# FC_RGB.net
KiCad netlist of a schematic drawn in Altium Designer
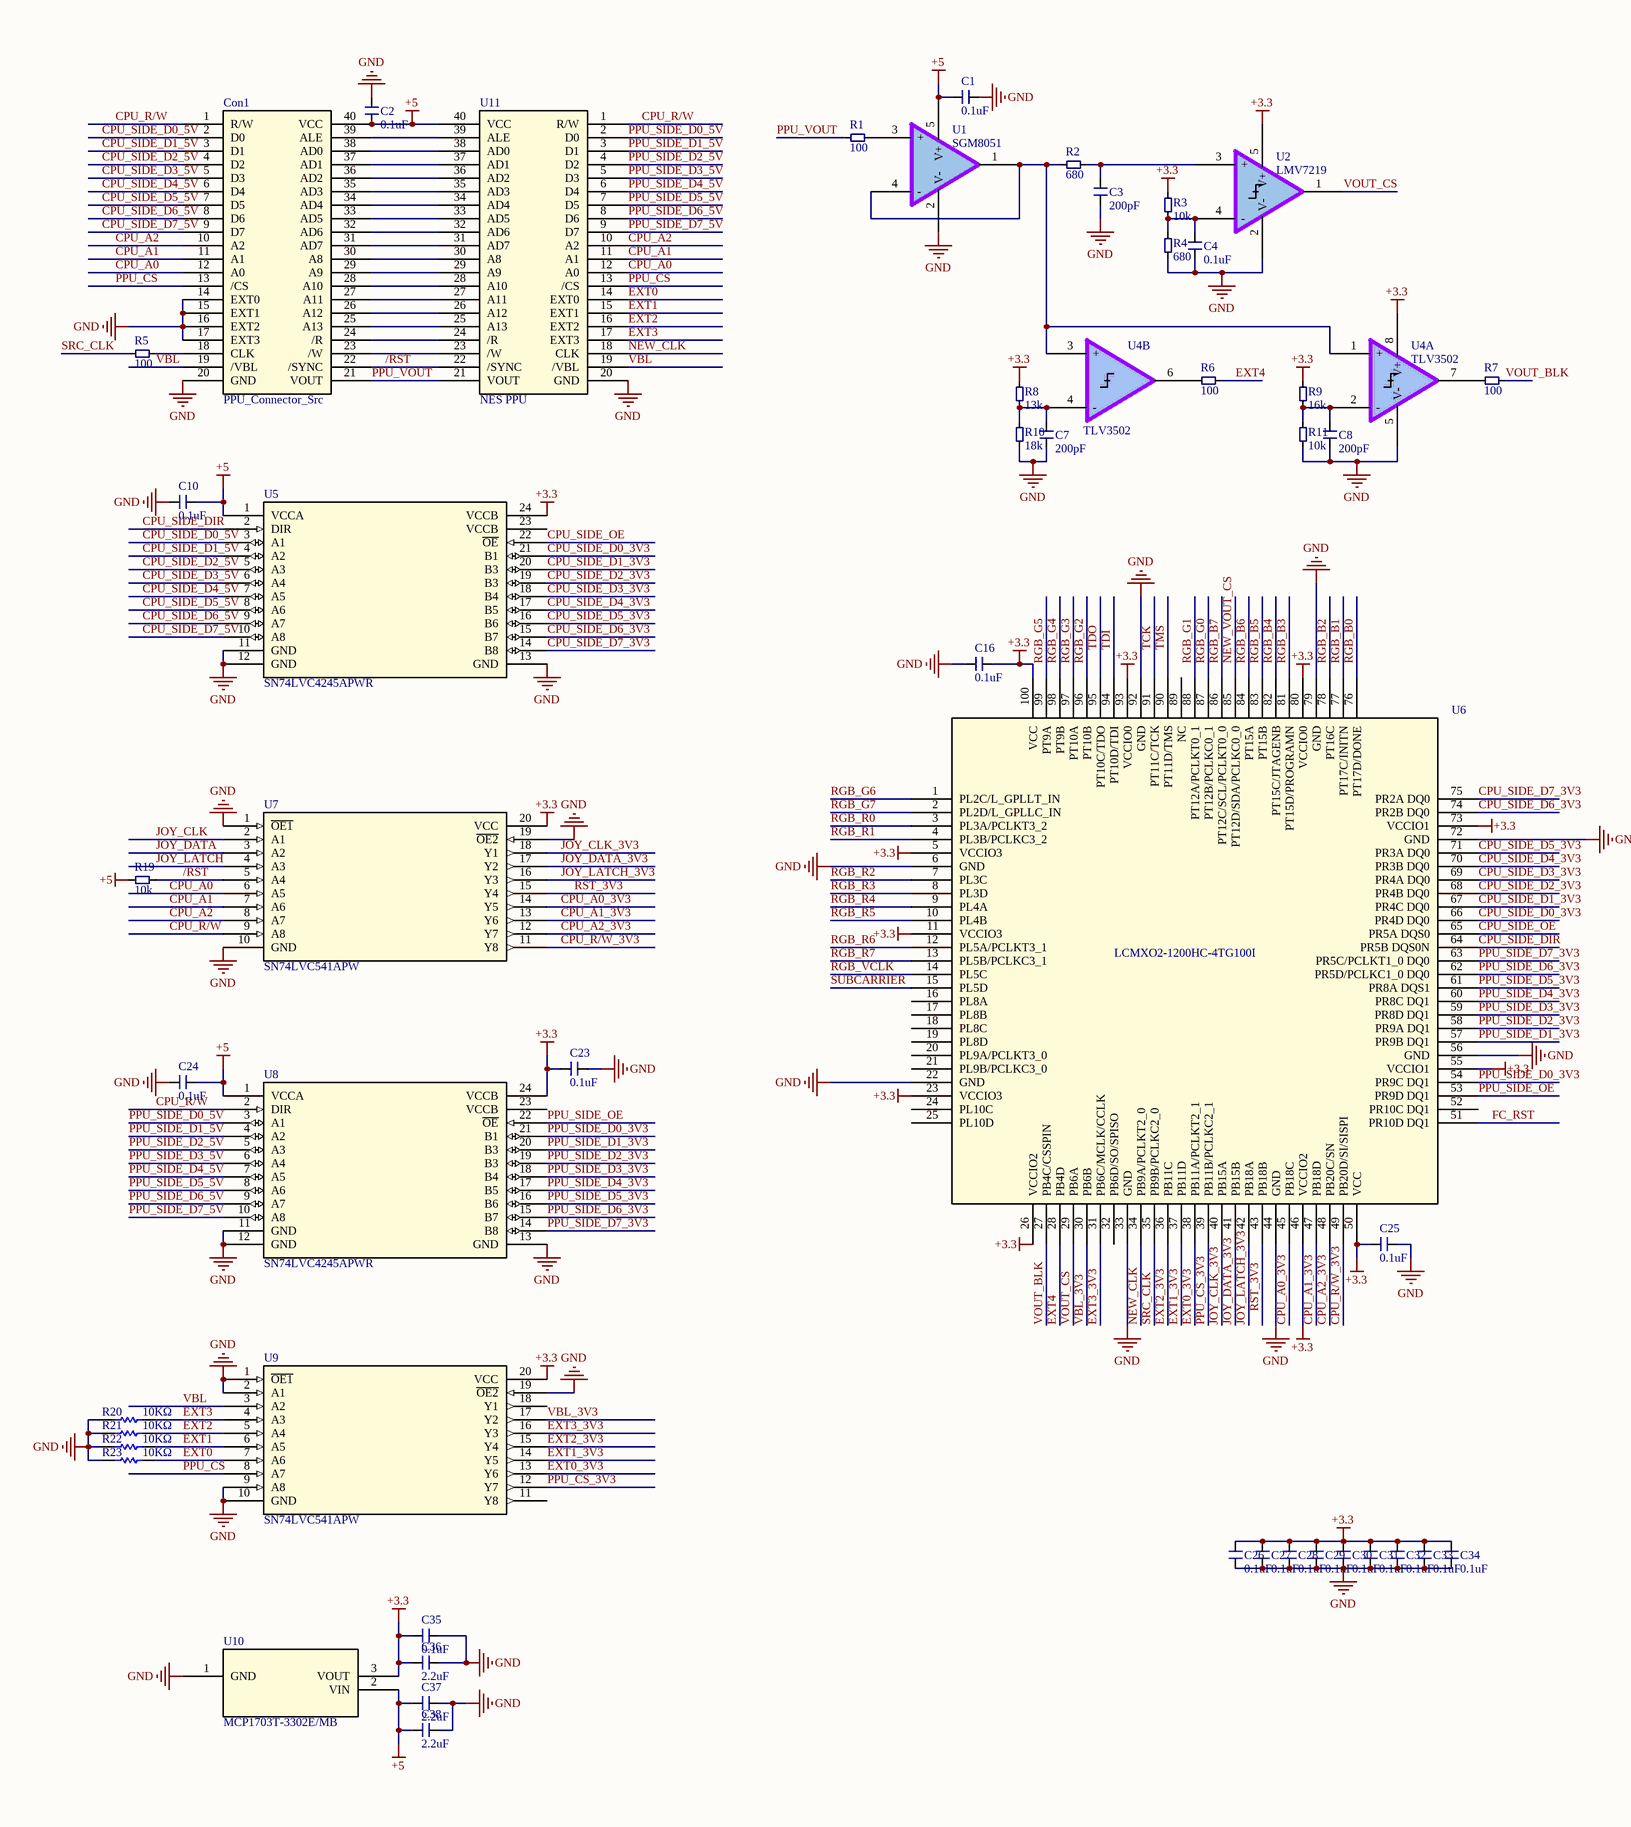
[diagram p0: FC_RGB.SchDoc, left]
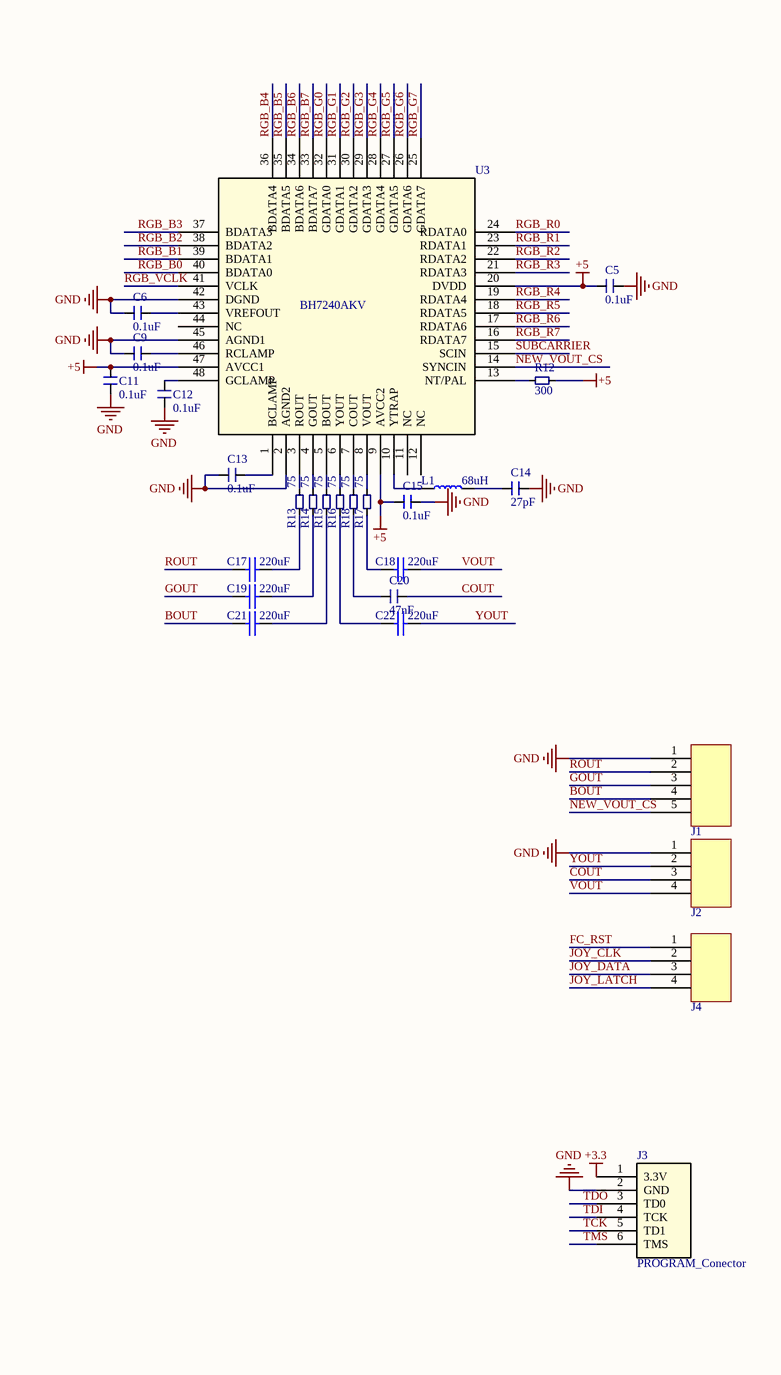
[diagram p1: FC_RGB.SchDoc, right]

(export (version "E")
  (design (tool "Eeschema 10.0.6"))
  (components
    (comp (ref "C1")
      (value "0.1uF")
      (footprint "C0402")
      (fields (field (name "Comment") "Cap"))
      (libsource (lib "Au") (part "CAP"))
    )
    (comp (ref "C2")
      (value "0.1uF")
      (footprint "C0805")
      (fields (field (name "Comment") "Cap"))
      (libsource (lib "Au") (part "CAP"))
    )
    (comp (ref "C3")
      (value "200pF")
      (footprint "C0402")
      (fields (field (name "Comment") "Cap"))
      (libsource (lib "Au") (part "CAP"))
    )
    (comp (ref "C4")
      (value "0.1uF")
      (footprint "C0402")
      (fields (field (name "Comment") "Cap"))
      (libsource (lib "Au") (part "CAP"))
    )
    (comp (ref "C5")
      (value "0.1uF")
      (footprint "C0402")
      (fields (field (name "Comment") "CAP"))
      (libsource (lib "Au") (part "CAP"))
    )
    (comp (ref "C6")
      (value "0.1uF")
      (footprint "C0402")
      (fields (field (name "Comment") "CAP"))
      (libsource (lib "Au") (part "CAP"))
    )
    (comp (ref "C7")
      (value "200pF")
      (footprint "C0402")
      (fields (field (name "Comment") "Cap"))
      (libsource (lib "Au") (part "CAP"))
    )
    (comp (ref "C8")
      (value "200pF")
      (footprint "C0402")
      (fields (field (name "Comment") "Cap"))
      (libsource (lib "Au") (part "CAP"))
    )
    (comp (ref "C9")
      (value "0.1uF")
      (footprint "C0402")
      (fields (field (name "Comment") "CAP"))
      (libsource (lib "Au") (part "CAP"))
    )
    (comp (ref "C10")
      (value "0.1uF")
      (footprint "C0402")
      (fields (field (name "Comment") "CAP"))
      (libsource (lib "Au") (part "CAP"))
    )
    (comp (ref "C11")
      (value "0.1uF")
      (footprint "C0402")
      (fields (field (name "Comment") "CAP"))
      (libsource (lib "Au") (part "CAP"))
    )
    (comp (ref "C12")
      (value "0.1uF")
      (footprint "C0402")
      (fields (field (name "Comment") "CAP"))
      (libsource (lib "Au") (part "CAP"))
    )
    (comp (ref "C13")
      (value "0.1uF")
      (footprint "C0402")
      (fields (field (name "Comment") "CAP"))
      (libsource (lib "Au") (part "CAP"))
    )
    (comp (ref "C14")
      (value "27pF")
      (footprint "C0402")
      (fields (field (name "Comment") "CAP"))
      (libsource (lib "Au") (part "CAP"))
    )
    (comp (ref "C15")
      (value "0.1uF")
      (footprint "C0402")
      (fields (field (name "Comment") "CAP"))
      (libsource (lib "Au") (part "CAP"))
    )
    (comp (ref "C16")
      (value "0.1uF")
      (footprint "C0402")
      (fields (field (name "Comment") "Cap"))
      (libsource (lib "Au") (part "CAP"))
    )
    (comp (ref "C17")
      (value "220uF")
      (footprint "C 1206_L")
      (description "No Description Available")
      (fields
        (field (name "MANUFACTURER_PART_NUMBER") "C0603X394K4RACAUTO")
        (field (name "COPYRIGHT") "Copyright (C) 2022 Ultra Librarian. All rights reserved.")
      )
      (libsource (lib "FC_Extends") (part "C1206"))
    )
    (comp (ref "C18")
      (value "220uF")
      (footprint "C 1206_L")
      (description "No Description Available")
      (fields
        (field (name "MANUFACTURER_PART_NUMBER") "C0603X394K4RACAUTO")
        (field (name "COPYRIGHT") "Copyright (C) 2022 Ultra Librarian. All rights reserved.")
      )
      (libsource (lib "FC_Extends") (part "C1206"))
    )
    (comp (ref "C19")
      (value "220uF")
      (footprint "C 1206_L")
      (description "No Description Available")
      (fields
        (field (name "MANUFACTURER_PART_NUMBER") "C0603X394K4RACAUTO")
        (field (name "COPYRIGHT") "Copyright (C) 2022 Ultra Librarian. All rights reserved.")
      )
      (libsource (lib "FC_Extends") (part "C1206"))
    )
    (comp (ref "C20")
      (value "47nF")
      (footprint "C0402")
      (fields (field (name "Comment") "CAP"))
      (libsource (lib "Au") (part "CAP"))
    )
    (comp (ref "C21")
      (value "220uF")
      (footprint "C 1206_L")
      (description "No Description Available")
      (fields
        (field (name "MANUFACTURER_PART_NUMBER") "C0603X394K4RACAUTO")
        (field (name "COPYRIGHT") "Copyright (C) 2022 Ultra Librarian. All rights reserved.")
      )
      (libsource (lib "FC_Extends") (part "C1206"))
    )
    (comp (ref "C22")
      (value "220uF")
      (footprint "C 1206_L")
      (description "No Description Available")
      (fields
        (field (name "MANUFACTURER_PART_NUMBER") "C0603X394K4RACAUTO")
        (field (name "COPYRIGHT") "Copyright (C) 2022 Ultra Librarian. All rights reserved.")
      )
      (libsource (lib "FC_Extends") (part "C1206"))
    )
    (comp (ref "C23")
      (value "0.1uF")
      (footprint "C0402")
      (fields (field (name "Comment") "CAP"))
      (libsource (lib "Au") (part "CAP"))
    )
    (comp (ref "C24")
      (value "0.1uF")
      (footprint "C0402")
      (fields (field (name "Comment") "CAP"))
      (libsource (lib "Au") (part "CAP"))
    )
    (comp (ref "C25")
      (value "0.1uF")
      (footprint "C0402")
      (fields (field (name "Comment") "Cap"))
      (libsource (lib "Au") (part "CAP"))
    )
    (comp (ref "C26")
      (value "0.1uF")
      (footprint "C0402")
      (fields (field (name "Comment") "CAP"))
      (libsource (lib "Au") (part "CAP"))
    )
    (comp (ref "C27")
      (value "0.1uF")
      (footprint "C0402")
      (fields (field (name "Comment") "CAP"))
      (libsource (lib "Au") (part "CAP"))
    )
    (comp (ref "C28")
      (value "0.1uF")
      (footprint "C0402")
      (fields (field (name "Comment") "CAP"))
      (libsource (lib "Au") (part "CAP"))
    )
    (comp (ref "C29")
      (value "0.1uF")
      (footprint "C0402")
      (fields (field (name "Comment") "CAP"))
      (libsource (lib "Au") (part "CAP"))
    )
    (comp (ref "C30")
      (value "0.1uF")
      (footprint "C0402")
      (fields (field (name "Comment") "CAP"))
      (libsource (lib "Au") (part "CAP"))
    )
    (comp (ref "C31")
      (value "0.1uF")
      (footprint "C0402")
      (fields (field (name "Comment") "CAP"))
      (libsource (lib "Au") (part "CAP"))
    )
    (comp (ref "C32")
      (value "0.1uF")
      (footprint "C0402")
      (fields (field (name "Comment") "CAP"))
      (libsource (lib "Au") (part "CAP"))
    )
    (comp (ref "C33")
      (value "0.1uF")
      (footprint "C0402")
      (fields (field (name "Comment") "CAP"))
      (libsource (lib "Au") (part "CAP"))
    )
    (comp (ref "C34")
      (value "0.1uF")
      (footprint "C0402")
      (fields (field (name "Comment") "CAP"))
      (libsource (lib "Au") (part "CAP"))
    )
    (comp (ref "C35")
      (value "0.1uF")
      (footprint "C0603")
      (fields (field (name "Comment") "Cap"))
      (libsource (lib "Au") (part "CAP"))
    )
    (comp (ref "C36")
      (value "2.2uF")
      (footprint "C0603")
      (fields (field (name "Comment") "Cap"))
      (libsource (lib "Au") (part "CAP"))
    )
    (comp (ref "C37")
      (value "2.2uF")
      (footprint "C0805")
      (fields (field (name "Comment") "Cap"))
      (libsource (lib "Au") (part "CAP"))
    )
    (comp (ref "C38")
      (value "2.2uF")
      (footprint "C0805")
      (fields (field (name "Comment") "Cap"))
      (libsource (lib "Au") (part "CAP"))
    )
    (comp (ref "Con1")
      (value "PPU_Connector_Src")
      (footprint "DIP40_SRC")
      (libsource (lib "FC_Extends") (part "PPU_Connector_Src"))
    )
    (comp (ref "J1") (value "CN") (footprint "CN5_1.25_90") (libsource (lib "Au") (part "CN5")))
    (comp (ref "J2") (value "CN") (footprint "CN4_1.25_90") (libsource (lib "Au") (part "CN4")))
    (comp (ref "J3")
      (value "PROGRAM_Conector")
      (footprint "CON_PROGRAM")
      (libsource (lib "FC_Extends") (part "PROGRAM_Conector"))
    )
    (comp (ref "J4") (value "CN") (footprint "CN4_1.25_90") (libsource (lib "Au") (part "CN4")))
    (comp (ref "L1") (value "68uH") (footprint "L 0805") (libsource (lib "FC_Extends") (part "L0805")))
    (comp (ref "R1")
      (value "100")
      (footprint "R-0402")
      (fields (field (name "Comment") "RES_SMD"))
      (libsource (lib "Au") (part "RES_SMD"))
    )
    (comp (ref "R2")
      (value "680")
      (footprint "R-0402")
      (fields (field (name "Comment") "RES_SMD"))
      (libsource (lib "Au") (part "RES_SMD"))
    )
    (comp (ref "R3")
      (value "10k")
      (footprint "R-0402")
      (fields (field (name "Comment") "RES_SMD"))
      (libsource (lib "Au") (part "RES_SMD"))
    )
    (comp (ref "R4")
      (value "680")
      (footprint "R-0402")
      (fields (field (name "Comment") "RES_SMD"))
      (libsource (lib "Au") (part "RES_SMD"))
    )
    (comp (ref "R5")
      (value "100")
      (footprint "R-0402")
      (fields (field (name "Comment") "RES_SMD"))
      (libsource (lib "Au") (part "RES_SMD"))
    )
    (comp (ref "R6")
      (value "100")
      (footprint "R-0402")
      (fields (field (name "Comment") "RES_SMD"))
      (libsource (lib "Au") (part "RES_SMD"))
    )
    (comp (ref "R7")
      (value "100")
      (footprint "R-0402")
      (fields (field (name "Comment") "RES_SMD"))
      (libsource (lib "Au") (part "RES_SMD"))
    )
    (comp (ref "R8")
      (value "13k")
      (footprint "R-0402")
      (fields (field (name "Comment") "RES_SMD"))
      (libsource (lib "Au") (part "RES_SMD"))
    )
    (comp (ref "R9")
      (value "16k")
      (footprint "R-0402")
      (fields (field (name "Comment") "RES_SMD"))
      (libsource (lib "Au") (part "RES_SMD"))
    )
    (comp (ref "R10")
      (value "18k")
      (footprint "R-0402")
      (fields (field (name "Comment") "RES_SMD"))
      (libsource (lib "Au") (part "RES_SMD"))
    )
    (comp (ref "R11")
      (value "10k")
      (footprint "R-0402")
      (fields (field (name "Comment") "RES_SMD"))
      (libsource (lib "Au") (part "RES_SMD"))
    )
    (comp (ref "R12")
      (value "300")
      (footprint "R-0402")
      (fields (field (name "Comment") "RES_SMD"))
      (libsource (lib "Au") (part "RES_SMD"))
    )
    (comp (ref "R13")
      (value "75")
      (footprint "R-0402")
      (fields (field (name "Comment") "RES_SMD"))
      (libsource (lib "Au") (part "RES_SMD"))
    )
    (comp (ref "R14")
      (value "75")
      (footprint "R-0402")
      (fields (field (name "Comment") "RES_SMD"))
      (libsource (lib "Au") (part "RES_SMD"))
    )
    (comp (ref "R15")
      (value "75")
      (footprint "R-0402")
      (fields (field (name "Comment") "RES_SMD"))
      (libsource (lib "Au") (part "RES_SMD"))
    )
    (comp (ref "R16")
      (value "75")
      (footprint "R-0402")
      (fields (field (name "Comment") "RES_SMD"))
      (libsource (lib "Au") (part "RES_SMD"))
    )
    (comp (ref "R17")
      (value "75")
      (footprint "R-0402")
      (fields (field (name "Comment") "RES_SMD"))
      (libsource (lib "Au") (part "RES_SMD"))
    )
    (comp (ref "R18")
      (value "75")
      (footprint "R-0402")
      (fields (field (name "Comment") "RES_SMD"))
      (libsource (lib "Au") (part "RES_SMD"))
    )
    (comp (ref "R19")
      (value "10k")
      (footprint "R-0402")
      (fields (field (name "Comment") "RES_SMD"))
      (libsource (lib "Au") (part "RES_SMD"))
    )
    (comp (ref "R20")
      (value "10KΩ")
      (footprint "0603_R")
      (description "No Description Available")
      (fields
        (field (name "MANUFACTURER_PART_NUMBER") "RC0603FR-07200RL")
        (field (name "COPYRIGHT") "Copyright (C) 2022 Ultra Librarian. All rights reserved.")
      )
      (libsource (lib "FC_Extends") (part "R0603"))
    )
    (comp (ref "R21")
      (value "10KΩ")
      (footprint "0603_R")
      (description "No Description Available")
      (fields
        (field (name "MANUFACTURER_PART_NUMBER") "RC0603FR-07200RL")
        (field (name "COPYRIGHT") "Copyright (C) 2022 Ultra Librarian. All rights reserved.")
      )
      (libsource (lib "FC_Extends") (part "R0603"))
    )
    (comp (ref "R22")
      (value "10KΩ")
      (footprint "0603_R")
      (description "No Description Available")
      (fields
        (field (name "MANUFACTURER_PART_NUMBER") "RC0603FR-07200RL")
        (field (name "COPYRIGHT") "Copyright (C) 2022 Ultra Librarian. All rights reserved.")
      )
      (libsource (lib "FC_Extends") (part "R0603"))
    )
    (comp (ref "R23")
      (value "10KΩ")
      (footprint "0603_R")
      (description "No Description Available")
      (fields
        (field (name "MANUFACTURER_PART_NUMBER") "RC0603FR-07200RL")
        (field (name "COPYRIGHT") "Copyright (C) 2022 Ultra Librarian. All rights reserved.")
      )
      (libsource (lib "FC_Extends") (part "R0603"))
    )
    (comp (ref "U1")
      (value "SGM8051")
      (footprint "SOT-23-5")
      (description "High Speed OpAmp")
      (libsource (lib "Au") (part "SGM8051"))
    )
    (comp (ref "U2")
      (value "LMV7219")
      (footprint "SOT-23-5")
      (description "High Speed Comparator")
      (libsource (lib "Au") (part "LMV7219"))
    )
    (comp (ref "U3")
      (value "BH7240AKV")
      (footprint "LQFP48-7*7")
      (description "No Description Available")
      (fields
        (field (name "MANUFACTURER_PART_NUMBER") "ADV7123JSTZ330")
        (field (name "COPYRIGHT") "Copyright (C) 2022 Ultra Librarian. All rights reserved.")
      )
      (libsource (lib "FC_Extends") (part "BH7240AKV"))
    )
    (comp (ref "U4")
      (value "TLV3502")
      (footprint "SOP-8-SMALL")
      (description "4.5ns Dual High-Speed Comparator")
      (libsource (lib "Au") (part "TLV3502"))
    )
    (comp (ref "U5")
      (value "SN74LVC4245APWR")
      (footprint "TSSOP24")
      (description "LJ245A")
      (fields (field (name "COPYRIGHT") "Copyright (C) 2022 Ultra Librarian. All rights reserved."))
      (libsource (lib "Au") (part "74LVC4245"))
    )
    (comp (ref "U6")
      (value "LCMXO2-1200HC-4TG100I")
      (footprint "TQFP100_LAT")
      (description "No Description Available")
      (fields (field (name "COPYRIGHT") "Copyright (C) 2023 Ultra Librarian. All rights reserved."))
      (libsource (lib "FC_Extends") (part "LCMXO2-1200HC"))
    )
    (comp (ref "U7")
      (value "SN74LVC541APW")
      (footprint "TSSOP20")
      (description "LC541A")
      (fields (field (name "COPYRIGHT") "Copyright (C) 2022 Ultra Librarian. All rights reserved."))
      (libsource (lib "Au") (part "74LVC541"))
    )
    (comp (ref "U8")
      (value "SN74LVC4245APWR")
      (footprint "TSSOP24")
      (description "LJ245A")
      (fields (field (name "COPYRIGHT") "Copyright (C) 2022 Ultra Librarian. All rights reserved."))
      (libsource (lib "Au") (part "74LVC4245"))
    )
    (comp (ref "U9")
      (value "SN74LVC541APW")
      (footprint "TSSOP20")
      (description "LC541A")
      (fields (field (name "COPYRIGHT") "Copyright (C) 2022 Ultra Librarian. All rights reserved."))
      (libsource (lib "Au") (part "74LVC541"))
    )
    (comp (ref "U10")
      (value "MCP1703T-3302E/MB")
      (footprint "SOT-89_3MC_MCH")
      (description "No Description Available")
      (fields (field (name "COPYRIGHT") "Copyright (C) 2022 Ultra Librarian. All rights reserved."))
      (libsource (lib "FC_Extends") (part "MCP1703T-3302E/MB"))
    )
    (comp (ref "U11")
      (value "NES PPU")
      (footprint "PDIP-40-BP")
      (description "NES PPU RP2C02")
      (libsource (lib "Au") (part "RP2C02"))
    )
  )
  (nets
    (net (code "1") (name "+3.3") (class "Default")
      (node (ref "C16") (pin "2") (pintype "power_in"))
      (node (ref "C23") (pin "2") (pintype "power_in"))
      (node (ref "C25") (pin "1") (pintype "power_in"))
      (node (ref "C26") (pin "1") (pintype "power_in"))
      (node (ref "C27") (pin "1") (pintype "power_in"))
      (node (ref "C28") (pin "1") (pintype "power_in"))
      (node (ref "C29") (pin "1") (pintype "power_in"))
      (node (ref "C30") (pin "1") (pintype "power_in"))
      (node (ref "C31") (pin "1") (pintype "power_in"))
      (node (ref "C32") (pin "1") (pintype "power_in"))
      (node (ref "C33") (pin "1") (pintype "power_in"))
      (node (ref "C34") (pin "1") (pintype "power_in"))
      (node (ref "C35") (pin "1") (pintype "power_in"))
      (node (ref "C36") (pin "1") (pintype "power_in"))
      (node (ref "J3") (pin "1") (pinfunction "3.3V_1") (pintype "passive"))
      (node (ref "R3") (pin "2") (pintype "passive"))
      (node (ref "R8") (pin "2") (pintype "passive"))
      (node (ref "R9") (pin "2") (pintype "passive"))
      (node (ref "U10") (pin "3") (pinfunction "VOUT_3") (pintype "passive"))
      (node (ref "U2") (pin "5") (pinfunction "V+_5") (pintype "passive"))
      (node (ref "U4") (pin "8") (pinfunction "V+_8") (pintype "passive"))
      (node (ref "U5") (pin "24") (pinfunction "VCCB_24") (pintype "power_in"))
      (node (ref "U6") (pin "100") (pinfunction "VCC_100") (pintype "power_in"))
      (node (ref "U6") (pin "11") (pinfunction "VCCIO3_11") (pintype "power_in"))
      (node (ref "U6") (pin "23") (pinfunction "VCCIO3_23") (pintype "power_in"))
      (node (ref "U6") (pin "26") (pinfunction "VCCIO2_26") (pintype "power_in"))
      (node (ref "U6") (pin "46") (pinfunction "VCCIO2_46") (pintype "power_in"))
      (node (ref "U6") (pin "5") (pinfunction "VCCIO3_5") (pintype "power_in"))
      (node (ref "U6") (pin "50") (pinfunction "VCC_50") (pintype "power_in"))
      (node (ref "U6") (pin "55") (pinfunction "VCCIO1_55") (pintype "power_in"))
      (node (ref "U6") (pin "73") (pinfunction "VCCIO1_73") (pintype "power_in"))
      (node (ref "U6") (pin "80") (pinfunction "VCCIO0_80") (pintype "power_in"))
      (node (ref "U6") (pin "93") (pinfunction "VCCIO0_93") (pintype "power_in"))
      (node (ref "U7") (pin "20") (pinfunction "VCC_20") (pintype "power_in"))
      (node (ref "U8") (pin "24") (pinfunction "VCCB_24") (pintype "power_in"))
      (node (ref "U9") (pin "20") (pinfunction "VCC_20") (pintype "power_in"))
    )
    (net (code "2") (name "+5") (class "Default")
      (node (ref "C1") (pin "1") (pintype "power_in"))
      (node (ref "C10") (pin "1") (pintype "power_in"))
      (node (ref "C11") (pin "2") (pintype "power_in"))
      (node (ref "C15") (pin "2") (pintype "power_in"))
      (node (ref "C2") (pin "1") (pintype "power_in"))
      (node (ref "C24") (pin "1") (pintype "power_in"))
      (node (ref "C37") (pin "1") (pintype "power_in"))
      (node (ref "C38") (pin "1") (pintype "power_in"))
      (node (ref "C5") (pin "2") (pintype "power_in"))
      (node (ref "Con1") (pin "40") (pinfunction "VCC_40") (pintype "passive"))
      (node (ref "R12") (pin "1") (pintype "passive"))
      (node (ref "R19") (pin "2") (pintype "passive"))
      (node (ref "U1") (pin "5") (pinfunction "V+_5") (pintype "passive"))
      (node (ref "U10") (pin "2") (pinfunction "VIN_2") (pintype "passive"))
      (node (ref "U11") (pin "40") (pinfunction "VCC_40") (pintype "passive"))
      (node (ref "U3") (pin "20") (pinfunction "DVDD_20") (pintype "passive"))
      (node (ref "U3") (pin "47") (pinfunction "AVCC1_47") (pintype "passive"))
      (node (ref "U3") (pin "9") (pinfunction "AVCC2_9") (pintype "passive"))
      (node (ref "U5") (pin "1") (pinfunction "VCCA_1") (pintype "power_in"))
      (node (ref "U8") (pin "1") (pinfunction "VCCA_1") (pintype "power_in"))
    )
    (net (code "3") (name "/BOUT") (class "Default")
      (node (ref "C21") (pin "2") (pinfunction "2_2") (pintype "passive"))
      (node (ref "J1") (pin "4") (pintype "passive"))
    )
    (net (code "4") (name "/COUT") (class "Default")
      (node (ref "C20") (pin "1") (pintype "power_in"))
      (node (ref "J2") (pin "3") (pintype "passive"))
    )
    (net (code "5") (name "/CPU_A0") (class "Default")
      (node (ref "Con1") (pin "12") (pinfunction "A0_12") (pintype "passive"))
      (node (ref "U11") (pin "12") (pinfunction "A0_12") (pintype "passive"))
      (node (ref "U7") (pin "6") (pinfunction "A5_6") (pintype "input"))
    )
    (net (code "6") (name "/CPU_A0_3V3") (class "Default")
      (node (ref "U6") (pin "45") (pinfunction "PB18C_45") (pintype "passive"))
      (node (ref "U7") (pin "14") (pinfunction "Y5_14") (pintype "output"))
    )
    (net (code "7") (name "/CPU_A1") (class "Default")
      (node (ref "Con1") (pin "11") (pinfunction "A1_11") (pintype "passive"))
      (node (ref "U11") (pin "11") (pinfunction "A1_11") (pintype "passive"))
      (node (ref "U7") (pin "7") (pinfunction "A6_7") (pintype "input"))
    )
    (net (code "8") (name "/CPU_A1_3V3") (class "Default")
      (node (ref "U6") (pin "47") (pinfunction "PB18D_47") (pintype "passive"))
      (node (ref "U7") (pin "13") (pinfunction "Y6_13") (pintype "output"))
    )
    (net (code "9") (name "/CPU_A2") (class "Default")
      (node (ref "Con1") (pin "10") (pinfunction "A2_10") (pintype "passive"))
      (node (ref "U11") (pin "10") (pinfunction "A2_10") (pintype "passive"))
      (node (ref "U7") (pin "8") (pinfunction "A7_8") (pintype "input"))
    )
    (net (code "10") (name "/CPU_A2_3V3") (class "Default")
      (node (ref "U6") (pin "48") (pinfunction "PB20C/SN_48") (pintype "passive"))
      (node (ref "U7") (pin "12") (pinfunction "Y7_12") (pintype "output"))
    )
    (net (code "11") (name "/CPU_R{slash}W") (class "Default")
      (node (ref "Con1") (pin "1") (pinfunction "R/W_1") (pintype "passive"))
      (node (ref "U11") (pin "1") (pinfunction "R/W_1") (pintype "passive"))
      (node (ref "U7") (pin "9") (pinfunction "A8_9") (pintype "input"))
      (node (ref "U8") (pin "2") (pinfunction "DIR_2") (pintype "input"))
    )
    (net (code "12") (name "/CPU_R{slash}W_3V3") (class "Default")
      (node (ref "U6") (pin "49") (pinfunction "PB20D/SI/SISPI_49") (pintype "passive"))
      (node (ref "U7") (pin "11") (pinfunction "Y8_11") (pintype "output"))
    )
    (net (code "13") (name "/CPU_SIDE_D0_3V3") (class "Default")
      (node (ref "U5") (pin "21") (pinfunction "B1_21") (pintype "bidirectional"))
      (node (ref "U6") (pin "66") (pinfunction "PR4D_DQ0_66") (pintype "passive"))
    )
    (net (code "14") (name "/CPU_SIDE_D0_5V") (class "Default")
      (node (ref "Con1") (pin "2") (pinfunction "D0_2") (pintype "passive"))
      (node (ref "U5") (pin "3") (pinfunction "A1_3") (pintype "bidirectional"))
    )
    (net (code "15") (name "/CPU_SIDE_D1_3V3") (class "Default")
      (node (ref "U5") (pin "20") (pinfunction "B3_20") (pintype "bidirectional"))
      (node (ref "U6") (pin "67") (pinfunction "PR4C_DQ0_67") (pintype "passive"))
    )
    (net (code "16") (name "/CPU_SIDE_D1_5V") (class "Default")
      (node (ref "Con1") (pin "3") (pinfunction "D1_3") (pintype "passive"))
      (node (ref "U5") (pin "4") (pinfunction "A2_4") (pintype "bidirectional"))
    )
    (net (code "17") (name "/CPU_SIDE_D2_3V3") (class "Default")
      (node (ref "U5") (pin "19") (pinfunction "B3_19") (pintype "bidirectional"))
      (node (ref "U6") (pin "68") (pinfunction "PR4B_DQ0_68") (pintype "passive"))
    )
    (net (code "18") (name "/CPU_SIDE_D2_5V") (class "Default")
      (node (ref "Con1") (pin "4") (pinfunction "D2_4") (pintype "passive"))
      (node (ref "U5") (pin "5") (pinfunction "A3_5") (pintype "bidirectional"))
    )
    (net (code "19") (name "/CPU_SIDE_D3_3V3") (class "Default")
      (node (ref "U5") (pin "18") (pinfunction "B4_18") (pintype "bidirectional"))
      (node (ref "U6") (pin "69") (pinfunction "PR4A_DQ0_69") (pintype "passive"))
    )
    (net (code "20") (name "/CPU_SIDE_D3_5V") (class "Default")
      (node (ref "Con1") (pin "5") (pinfunction "D3_5") (pintype "passive"))
      (node (ref "U5") (pin "6") (pinfunction "A4_6") (pintype "bidirectional"))
    )
    (net (code "21") (name "/CPU_SIDE_D4_3V3") (class "Default")
      (node (ref "U5") (pin "17") (pinfunction "B5_17") (pintype "bidirectional"))
      (node (ref "U6") (pin "70") (pinfunction "PR3B_DQ0_70") (pintype "passive"))
    )
    (net (code "22") (name "/CPU_SIDE_D4_5V") (class "Default")
      (node (ref "Con1") (pin "6") (pinfunction "D4_6") (pintype "passive"))
      (node (ref "U5") (pin "7") (pinfunction "A5_7") (pintype "bidirectional"))
    )
    (net (code "23") (name "/CPU_SIDE_D5_3V3") (class "Default")
      (node (ref "U5") (pin "16") (pinfunction "B6_16") (pintype "bidirectional"))
      (node (ref "U6") (pin "71") (pinfunction "PR3A_DQ0_71") (pintype "passive"))
    )
    (net (code "24") (name "/CPU_SIDE_D5_5V") (class "Default")
      (node (ref "Con1") (pin "7") (pinfunction "D5_7") (pintype "passive"))
      (node (ref "U5") (pin "8") (pinfunction "A6_8") (pintype "bidirectional"))
    )
    (net (code "25") (name "/CPU_SIDE_D6_3V3") (class "Default")
      (node (ref "U5") (pin "15") (pinfunction "B7_15") (pintype "bidirectional"))
      (node (ref "U6") (pin "74") (pinfunction "PR2B_DQ0_74") (pintype "passive"))
    )
    (net (code "26") (name "/CPU_SIDE_D6_5V") (class "Default")
      (node (ref "Con1") (pin "8") (pinfunction "D6_8") (pintype "passive"))
      (node (ref "U5") (pin "9") (pinfunction "A7_9") (pintype "bidirectional"))
    )
    (net (code "27") (name "/CPU_SIDE_D7_3V3") (class "Default")
      (node (ref "U5") (pin "14") (pinfunction "B8_14") (pintype "bidirectional"))
      (node (ref "U6") (pin "75") (pinfunction "PR2A_DQ0_75") (pintype "passive"))
    )
    (net (code "28") (name "/CPU_SIDE_D7_5V") (class "Default")
      (node (ref "Con1") (pin "9") (pinfunction "D7_9") (pintype "passive"))
      (node (ref "U5") (pin "10") (pinfunction "A8_10") (pintype "bidirectional"))
    )
    (net (code "29") (name "/CPU_SIDE_DIR") (class "Default")
      (node (ref "U5") (pin "2") (pinfunction "DIR_2") (pintype "input"))
      (node (ref "U6") (pin "64") (pinfunction "PR5B_DQS0N_64") (pintype "passive"))
    )
    (net (code "30") (name "/CPU_SIDE_OE") (class "Default")
      (node (ref "U5") (pin "22") (pinfunction "~{OE}_22") (pintype "input"))
      (node (ref "U6") (pin "65") (pinfunction "PR5A_DQS0_65") (pintype "passive"))
    )
    (net (code "31") (name "/EXT0") (class "Default")
      (node (ref "R23") (pin "2") (pinfunction "2_2") (pintype "passive"))
      (node (ref "U11") (pin "14") (pinfunction "EXT0_14") (pintype "passive"))
      (node (ref "U9") (pin "7") (pinfunction "A6_7") (pintype "input"))
    )
    (net (code "32") (name "/EXT0_3V3") (class "Default")
      (node (ref "U6") (pin "38") (pinfunction "PB11A/PCLKT2_1_38") (pintype "passive"))
      (node (ref "U9") (pin "13") (pinfunction "Y6_13") (pintype "output"))
    )
    (net (code "33") (name "/EXT1") (class "Default")
      (node (ref "R22") (pin "2") (pinfunction "2_2") (pintype "passive"))
      (node (ref "U11") (pin "15") (pinfunction "EXT1_15") (pintype "passive"))
      (node (ref "U9") (pin "6") (pinfunction "A5_6") (pintype "input"))
    )
    (net (code "34") (name "/EXT1_3V3") (class "Default")
      (node (ref "U6") (pin "37") (pinfunction "PB11D_37") (pintype "passive"))
      (node (ref "U9") (pin "14") (pinfunction "Y5_14") (pintype "output"))
    )
    (net (code "35") (name "/EXT2") (class "Default")
      (node (ref "R21") (pin "2") (pinfunction "2_2") (pintype "passive"))
      (node (ref "U11") (pin "16") (pinfunction "EXT2_16") (pintype "passive"))
      (node (ref "U9") (pin "5") (pinfunction "A4_5") (pintype "input"))
    )
    (net (code "36") (name "/EXT2_3V3") (class "Default")
      (node (ref "U6") (pin "36") (pinfunction "PB11C_36") (pintype "passive"))
      (node (ref "U9") (pin "15") (pinfunction "Y4_15") (pintype "output"))
    )
    (net (code "37") (name "/EXT3") (class "Default")
      (node (ref "R20") (pin "2") (pinfunction "2_2") (pintype "passive"))
      (node (ref "U11") (pin "17") (pinfunction "EXT3_17") (pintype "passive"))
      (node (ref "U9") (pin "4") (pinfunction "A3_4") (pintype "input"))
    )
    (net (code "38") (name "/EXT3_3V3") (class "Default")
      (node (ref "U6") (pin "31") (pinfunction "PB6C/MCLK/CCLK_31") (pintype "passive"))
      (node (ref "U9") (pin "16") (pinfunction "Y3_16") (pintype "output"))
    )
    (net (code "39") (name "/EXT4") (class "Default")
      (node (ref "R6") (pin "1") (pintype "passive"))
      (node (ref "U6") (pin "28") (pinfunction "PB4D_28") (pintype "passive"))
    )
    (net (code "40") (name "/FC_RST") (class "Default")
      (node (ref "J4") (pin "1") (pintype "passive"))
      (node (ref "U6") (pin "51") (pinfunction "PR10D_DQ1_51") (pintype "passive"))
    )
    (net (code "41") (name "/GOUT") (class "Default")
      (node (ref "C19") (pin "2") (pinfunction "2_2") (pintype "passive"))
      (node (ref "J1") (pin "3") (pintype "passive"))
    )
    (net (code "42") (name "/JOY_CLK") (class "Default")
      (node (ref "J4") (pin "2") (pintype "passive"))
      (node (ref "U7") (pin "2") (pinfunction "A1_2") (pintype "input"))
    )
    (net (code "43") (name "/JOY_CLK_3V3") (class "Default")
      (node (ref "U6") (pin "40") (pinfunction "PB15A_40") (pintype "passive"))
      (node (ref "U7") (pin "18") (pinfunction "Y1_18") (pintype "output"))
    )
    (net (code "44") (name "/JOY_DATA") (class "Default")
      (node (ref "J4") (pin "3") (pintype "passive"))
      (node (ref "U7") (pin "3") (pinfunction "A2_3") (pintype "input"))
    )
    (net (code "45") (name "/JOY_DATA_3V3") (class "Default")
      (node (ref "U6") (pin "41") (pinfunction "PB15B_41") (pintype "passive"))
      (node (ref "U7") (pin "17") (pinfunction "Y2_17") (pintype "output"))
    )
    (net (code "46") (name "/JOY_LATCH") (class "Default")
      (node (ref "J4") (pin "4") (pintype "passive"))
      (node (ref "U7") (pin "4") (pinfunction "A3_4") (pintype "input"))
    )
    (net (code "47") (name "/JOY_LATCH_3V3") (class "Default")
      (node (ref "U6") (pin "42") (pinfunction "PB18A_42") (pintype "passive"))
      (node (ref "U7") (pin "16") (pinfunction "Y3_16") (pintype "output"))
    )
    (net (code "48") (name "/NEW_CLK") (class "Default")
      (node (ref "U11") (pin "18") (pinfunction "CLK_18") (pintype "passive"))
      (node (ref "U6") (pin "34") (pinfunction "PB9A/PCLKT2_0_34") (pintype "passive"))
    )
    (net (code "49") (name "/NEW_VOUT_CS") (class "Default")
      (node (ref "J1") (pin "5") (pintype "passive"))
      (node (ref "U3") (pin "14") (pinfunction "SYNCIN_14") (pintype "passive"))
      (node (ref "U6") (pin "85") (pinfunction "PT12D/SDA/PCLKC0_0_85") (pintype "passive"))
    )
    (net (code "50") (name "/PPU_CS") (class "Default")
      (node (ref "Con1") (pin "13") (pinfunction "/CS_13") (pintype "passive"))
      (node (ref "U11") (pin "13") (pinfunction "/CS_13") (pintype "passive"))
      (node (ref "U9") (pin "8") (pinfunction "A7_8") (pintype "input"))
    )
    (net (code "51") (name "/PPU_CS_3V3") (class "Default")
      (node (ref "U6") (pin "39") (pinfunction "PB11B/PCLKC2_1_39") (pintype "passive"))
      (node (ref "U9") (pin "12") (pinfunction "Y7_12") (pintype "output"))
    )
    (net (code "52") (name "/PPU_SIDE_D0_3V3") (class "Default")
      (node (ref "U6") (pin "54") (pinfunction "PR9C_DQ1_54") (pintype "passive"))
      (node (ref "U8") (pin "21") (pinfunction "B1_21") (pintype "bidirectional"))
    )
    (net (code "53") (name "/PPU_SIDE_D0_5V") (class "Default")
      (node (ref "U11") (pin "2") (pinfunction "D0_2") (pintype "passive"))
      (node (ref "U8") (pin "3") (pinfunction "A1_3") (pintype "bidirectional"))
    )
    (net (code "54") (name "/PPU_SIDE_D1_3V3") (class "Default")
      (node (ref "U6") (pin "57") (pinfunction "PR9B_DQ1_57") (pintype "passive"))
      (node (ref "U8") (pin "20") (pinfunction "B3_20") (pintype "bidirectional"))
    )
    (net (code "55") (name "/PPU_SIDE_D1_5V") (class "Default")
      (node (ref "U11") (pin "3") (pinfunction "D1_3") (pintype "passive"))
      (node (ref "U8") (pin "4") (pinfunction "A2_4") (pintype "bidirectional"))
    )
    (net (code "56") (name "/PPU_SIDE_D2_3V3") (class "Default")
      (node (ref "U6") (pin "58") (pinfunction "PR9A_DQ1_58") (pintype "passive"))
      (node (ref "U8") (pin "19") (pinfunction "B3_19") (pintype "bidirectional"))
    )
    (net (code "57") (name "/PPU_SIDE_D2_5V") (class "Default")
      (node (ref "U11") (pin "4") (pinfunction "D2_4") (pintype "passive"))
      (node (ref "U8") (pin "5") (pinfunction "A3_5") (pintype "bidirectional"))
    )
    (net (code "58") (name "/PPU_SIDE_D3_3V3") (class "Default")
      (node (ref "U6") (pin "59") (pinfunction "PR8D_DQ1_59") (pintype "passive"))
      (node (ref "U8") (pin "18") (pinfunction "B4_18") (pintype "bidirectional"))
    )
    (net (code "59") (name "/PPU_SIDE_D3_5V") (class "Default")
      (node (ref "U11") (pin "5") (pinfunction "D3_5") (pintype "passive"))
      (node (ref "U8") (pin "6") (pinfunction "A4_6") (pintype "bidirectional"))
    )
    (net (code "60") (name "/PPU_SIDE_D4_3V3") (class "Default")
      (node (ref "U6") (pin "60") (pinfunction "PR8C_DQ1_60") (pintype "passive"))
      (node (ref "U8") (pin "17") (pinfunction "B5_17") (pintype "bidirectional"))
    )
    (net (code "61") (name "/PPU_SIDE_D4_5V") (class "Default")
      (node (ref "U11") (pin "6") (pinfunction "D4_6") (pintype "passive"))
      (node (ref "U8") (pin "7") (pinfunction "A5_7") (pintype "bidirectional"))
    )
    (net (code "62") (name "/PPU_SIDE_D5_3V3") (class "Default")
      (node (ref "U6") (pin "61") (pinfunction "PR8A_DQS1_61") (pintype "passive"))
      (node (ref "U8") (pin "16") (pinfunction "B6_16") (pintype "bidirectional"))
    )
    (net (code "63") (name "/PPU_SIDE_D5_5V") (class "Default")
      (node (ref "U11") (pin "7") (pinfunction "D5_7") (pintype "passive"))
      (node (ref "U8") (pin "8") (pinfunction "A6_8") (pintype "bidirectional"))
    )
    (net (code "64") (name "/PPU_SIDE_D6_3V3") (class "Default")
      (node (ref "U6") (pin "62") (pinfunction "PR5D/PCLKC1_0_DQ0_62") (pintype "passive"))
      (node (ref "U8") (pin "15") (pinfunction "B7_15") (pintype "bidirectional"))
    )
    (net (code "65") (name "/PPU_SIDE_D6_5V") (class "Default")
      (node (ref "U11") (pin "8") (pinfunction "D6_8") (pintype "passive"))
      (node (ref "U8") (pin "9") (pinfunction "A7_9") (pintype "bidirectional"))
    )
    (net (code "66") (name "/PPU_SIDE_D7_3V3") (class "Default")
      (node (ref "U6") (pin "63") (pinfunction "PR5C/PCLKT1_0_DQ0_63") (pintype "passive"))
      (node (ref "U8") (pin "14") (pinfunction "B8_14") (pintype "bidirectional"))
    )
    (net (code "67") (name "/PPU_SIDE_D7_5V") (class "Default")
      (node (ref "U11") (pin "9") (pinfunction "D7_9") (pintype "passive"))
      (node (ref "U8") (pin "10") (pinfunction "A8_10") (pintype "bidirectional"))
    )
    (net (code "68") (name "/PPU_SIDE_OE") (class "Default")
      (node (ref "U6") (pin "53") (pinfunction "PR9D_DQ1_53") (pintype "passive"))
      (node (ref "U8") (pin "22") (pinfunction "~{OE}_22") (pintype "input"))
    )
    (net (code "69") (name "/PPU_VOUT") (class "Default")
      (node (ref "Con1") (pin "21") (pinfunction "VOUT_21") (pintype "passive"))
      (node (ref "R1") (pin "1") (pintype "passive"))
      (node (ref "U11") (pin "21") (pinfunction "VOUT_21") (pintype "passive"))
    )
    (net (code "70") (name "/RGB_B0") (class "Default")
      (node (ref "U3") (pin "40") (pinfunction "BDATA0_40") (pintype "passive"))
      (node (ref "U6") (pin "76") (pinfunction "PT17D/DONE_76") (pintype "passive"))
    )
    (net (code "71") (name "/RGB_B1") (class "Default")
      (node (ref "U3") (pin "39") (pinfunction "BDATA1_39") (pintype "passive"))
      (node (ref "U6") (pin "77") (pinfunction "PT17C/INITN_77") (pintype "passive"))
    )
    (net (code "72") (name "/RGB_B2") (class "Default")
      (node (ref "U3") (pin "38") (pinfunction "BDATA2_38") (pintype "passive"))
      (node (ref "U6") (pin "78") (pinfunction "PT16C_78") (pintype "passive"))
    )
    (net (code "73") (name "/RGB_B3") (class "Default")
      (node (ref "U3") (pin "37") (pinfunction "BDATA3_37") (pintype "passive"))
      (node (ref "U6") (pin "81") (pinfunction "PT15D/PROGRAMN_81") (pintype "passive"))
    )
    (net (code "74") (name "/RGB_B4") (class "Default")
      (node (ref "U3") (pin "36") (pinfunction "BDATA4_36") (pintype "passive"))
      (node (ref "U6") (pin "82") (pinfunction "PT15C/JTAGENB_82") (pintype "passive"))
    )
    (net (code "75") (name "/RGB_B5") (class "Default")
      (node (ref "U3") (pin "35") (pinfunction "BDATA5_35") (pintype "passive"))
      (node (ref "U6") (pin "83") (pinfunction "PT15B_83") (pintype "passive"))
    )
    (net (code "76") (name "/RGB_B6") (class "Default")
      (node (ref "U3") (pin "34") (pinfunction "BDATA6_34") (pintype "passive"))
      (node (ref "U6") (pin "84") (pinfunction "PT15A_84") (pintype "passive"))
    )
    (net (code "77") (name "/RGB_B7") (class "Default")
      (node (ref "U3") (pin "33") (pinfunction "BDATA7_33") (pintype "passive"))
      (node (ref "U6") (pin "86") (pinfunction "PT12C/SCL/PCLKT0_0_86") (pintype "passive"))
    )
    (net (code "78") (name "/RGB_G0") (class "Default")
      (node (ref "U3") (pin "32") (pinfunction "GDATA0_32") (pintype "passive"))
      (node (ref "U6") (pin "87") (pinfunction "PT12B/PCLKC0_1_87") (pintype "passive"))
    )
    (net (code "79") (name "/RGB_G1") (class "Default")
      (node (ref "U3") (pin "31") (pinfunction "GDATA1_31") (pintype "passive"))
      (node (ref "U6") (pin "88") (pinfunction "PT12A/PCLKT0_1_88") (pintype "passive"))
    )
    (net (code "80") (name "/RGB_G2") (class "Default")
      (node (ref "U3") (pin "30") (pinfunction "GDATA2_30") (pintype "power_in"))
      (node (ref "U6") (pin "96") (pinfunction "PT10B_96") (pintype "passive"))
    )
    (net (code "81") (name "/RGB_G3") (class "Default")
      (node (ref "U3") (pin "29") (pinfunction "GDATA3_29") (pintype "power_in"))
      (node (ref "U6") (pin "97") (pinfunction "PT10A_97") (pintype "passive"))
    )
    (net (code "82") (name "/RGB_G4") (class "Default")
      (node (ref "U3") (pin "28") (pinfunction "GDATA4_28") (pintype "passive"))
      (node (ref "U6") (pin "98") (pinfunction "PT9B_98") (pintype "passive"))
    )
    (net (code "83") (name "/RGB_G5") (class "Default")
      (node (ref "U3") (pin "27") (pinfunction "GDATA5_27") (pintype "passive"))
      (node (ref "U6") (pin "99") (pinfunction "PT9A_99") (pintype "passive"))
    )
    (net (code "84") (name "/RGB_G6") (class "Default")
      (node (ref "U3") (pin "26") (pinfunction "GDATA6_26") (pintype "passive"))
      (node (ref "U6") (pin "1") (pinfunction "PL2C/L_GPLLT_IN_1") (pintype "passive"))
    )
    (net (code "85") (name "/RGB_G7") (class "Default")
      (node (ref "U3") (pin "25") (pinfunction "GDATA7_25") (pintype "passive"))
      (node (ref "U6") (pin "2") (pinfunction "PL2D/L_GPLLC_IN_2") (pintype "passive"))
    )
    (net (code "86") (name "/RGB_R0") (class "Default")
      (node (ref "U3") (pin "24") (pinfunction "RDATA0_24") (pintype "passive"))
      (node (ref "U6") (pin "3") (pinfunction "PL3A/PCLKT3_2_3") (pintype "passive"))
    )
    (net (code "87") (name "/RGB_R1") (class "Default")
      (node (ref "U3") (pin "23") (pinfunction "RDATA1_23") (pintype "passive"))
      (node (ref "U6") (pin "4") (pinfunction "PL3B/PCLKC3_2_4") (pintype "passive"))
    )
    (net (code "88") (name "/RGB_R2") (class "Default")
      (node (ref "U3") (pin "22") (pinfunction "RDATA2_22") (pintype "passive"))
      (node (ref "U6") (pin "7") (pinfunction "PL3C_7") (pintype "passive"))
    )
    (net (code "89") (name "/RGB_R3") (class "Default")
      (node (ref "U3") (pin "21") (pinfunction "RDATA3_21") (pintype "passive"))
      (node (ref "U6") (pin "8") (pinfunction "PL3D_8") (pintype "passive"))
    )
    (net (code "90") (name "/RGB_R4") (class "Default")
      (node (ref "U3") (pin "19") (pinfunction "RDATA4_19") (pintype "passive"))
      (node (ref "U6") (pin "9") (pinfunction "PL4A_9") (pintype "passive"))
    )
    (net (code "91") (name "/RGB_R5") (class "Default")
      (node (ref "U3") (pin "18") (pinfunction "RDATA5_18") (pintype "passive"))
      (node (ref "U6") (pin "10") (pinfunction "PL4B_10") (pintype "passive"))
    )
    (net (code "92") (name "/RGB_R6") (class "Default")
      (node (ref "U3") (pin "17") (pinfunction "RDATA6_17") (pintype "passive"))
      (node (ref "U6") (pin "12") (pinfunction "PL5A/PCLKT3_1_12") (pintype "passive"))
    )
    (net (code "93") (name "/RGB_R7") (class "Default")
      (node (ref "U3") (pin "16") (pinfunction "RDATA7_16") (pintype "passive"))
      (node (ref "U6") (pin "13") (pinfunction "PL5B/PCLKC3_1_13") (pintype "passive"))
    )
    (net (code "94") (name "/RGB_VCLK") (class "Default")
      (node (ref "U3") (pin "41") (pinfunction "VCLK_41") (pintype "passive"))
      (node (ref "U6") (pin "14") (pinfunction "PL5C_14") (pintype "passive"))
    )
    (net (code "95") (name "/ROUT") (class "Default")
      (node (ref "C17") (pin "2") (pinfunction "2_2") (pintype "passive"))
      (node (ref "J1") (pin "2") (pintype "passive"))
    )
    (net (code "96") (name "/RST_3V3") (class "Default")
      (node (ref "U6") (pin "43") (pinfunction "PB18B_43") (pintype "passive"))
      (node (ref "U7") (pin "15") (pinfunction "Y4_15") (pintype "output"))
    )
    (net (code "97") (name "/SRC_CLK") (class "Default")
      (node (ref "R5") (pin "2") (pintype "passive"))
      (node (ref "U6") (pin "35") (pinfunction "PB9B/PCLKC2_0_35") (pintype "passive"))
    )
    (net (code "98") (name "/SUBCARRIER") (class "Default")
      (node (ref "U3") (pin "15") (pinfunction "SCIN_15") (pintype "passive"))
      (node (ref "U6") (pin "15") (pinfunction "PL5D_15") (pintype "passive"))
    )
    (net (code "99") (name "/TCK") (class "Default")
      (node (ref "J3") (pin "5") (pinfunction "TD1_5") (pintype "passive"))
      (node (ref "U6") (pin "91") (pinfunction "PT11C/TCK_91") (pintype "passive"))
    )
    (net (code "100") (name "/TDI") (class "Default")
      (node (ref "J3") (pin "4") (pinfunction "TCK_4") (pintype "passive"))
      (node (ref "U6") (pin "94") (pinfunction "PT10D/TDI_94") (pintype "passive"))
    )
    (net (code "101") (name "/TDO") (class "Default")
      (node (ref "J3") (pin "3") (pinfunction "TD0_3") (pintype "passive"))
      (node (ref "U6") (pin "95") (pinfunction "PT10C/TDO_95") (pintype "passive"))
    )
    (net (code "102") (name "/TMS") (class "Default")
      (node (ref "J3") (pin "6") (pinfunction "TMS_6") (pintype "passive"))
      (node (ref "U6") (pin "90") (pinfunction "PT11D/TMS_90") (pintype "passive"))
    )
    (net (code "103") (name "/VBL") (class "Default")
      (node (ref "Con1") (pin "19") (pinfunction "/VBL_19") (pintype "passive"))
      (node (ref "U11") (pin "19") (pinfunction "/VBL_19") (pintype "passive"))
      (node (ref "U9") (pin "3") (pinfunction "A2_3") (pintype "input"))
    )
    (net (code "104") (name "/VBL_3V3") (class "Default")
      (node (ref "U6") (pin "30") (pinfunction "PB6B_30") (pintype "passive"))
      (node (ref "U9") (pin "17") (pinfunction "Y2_17") (pintype "output"))
    )
    (net (code "105") (name "/VOUT") (class "Default")
      (node (ref "C18") (pin "1") (pinfunction "1_1") (pintype "passive"))
      (node (ref "J2") (pin "4") (pintype "passive"))
    )
    (net (code "106") (name "/VOUT_BLK") (class "Default")
      (node (ref "R7") (pin "1") (pintype "passive"))
      (node (ref "U6") (pin "27") (pinfunction "PB4C/CSSPIN_27") (pintype "passive"))
    )
    (net (code "107") (name "/VOUT_CS") (class "Default")
      (node (ref "U2") (pin "1") (pintype "passive"))
      (node (ref "U6") (pin "29") (pinfunction "PB6A_29") (pintype "passive"))
    )
    (net (code "108") (name "/YOUT") (class "Default")
      (node (ref "C22") (pin "1") (pinfunction "1_1") (pintype "passive"))
      (node (ref "J2") (pin "2") (pintype "passive"))
    )
    (net (code "109") (name "/{slash}RST") (class "Default")
      (node (ref "Con1") (pin "22") (pinfunction "/SYNC_22") (pintype "passive"))
      (node (ref "R19") (pin "1") (pintype "passive"))
      (node (ref "U11") (pin "22") (pinfunction "/SYNC_22") (pintype "passive"))
      (node (ref "U7") (pin "5") (pinfunction "A4_5") (pintype "input"))
    )
    (net (code "110") (name "GND") (class "Default")
      (node (ref "C1") (pin "2") (pintype "power_in"))
      (node (ref "C10") (pin "2") (pintype "power_in"))
      (node (ref "C11") (pin "1") (pintype "power_in"))
      (node (ref "C12") (pin "1") (pintype "power_in"))
      (node (ref "C13") (pin "2") (pintype "power_in"))
      (node (ref "C14") (pin "1") (pintype "power_in"))
      (node (ref "C15") (pin "1") (pintype "power_in"))
      (node (ref "C16") (pin "1") (pintype "power_in"))
      (node (ref "C2") (pin "2") (pintype "power_in"))
      (node (ref "C23") (pin "1") (pintype "power_in"))
      (node (ref "C24") (pin "2") (pintype "power_in"))
      (node (ref "C25") (pin "2") (pintype "power_in"))
      (node (ref "C26") (pin "2") (pintype "power_in"))
      (node (ref "C27") (pin "2") (pintype "power_in"))
      (node (ref "C28") (pin "2") (pintype "power_in"))
      (node (ref "C29") (pin "2") (pintype "power_in"))
      (node (ref "C3") (pin "1") (pintype "power_in"))
      (node (ref "C30") (pin "2") (pintype "power_in"))
      (node (ref "C31") (pin "2") (pintype "power_in"))
      (node (ref "C32") (pin "2") (pintype "power_in"))
      (node (ref "C33") (pin "2") (pintype "power_in"))
      (node (ref "C34") (pin "2") (pintype "power_in"))
      (node (ref "C35") (pin "2") (pintype "power_in"))
      (node (ref "C36") (pin "2") (pintype "power_in"))
      (node (ref "C37") (pin "2") (pintype "power_in"))
      (node (ref "C38") (pin "2") (pintype "power_in"))
      (node (ref "C4") (pin "1") (pintype "power_in"))
      (node (ref "C5") (pin "1") (pintype "power_in"))
      (node (ref "C6") (pin "1") (pintype "power_in"))
      (node (ref "C7") (pin "1") (pintype "power_in"))
      (node (ref "C8") (pin "1") (pintype "power_in"))
      (node (ref "C9") (pin "1") (pintype "power_in"))
      (node (ref "Con1") (pin "14") (pinfunction "EXT0_14") (pintype "passive"))
      (node (ref "Con1") (pin "15") (pinfunction "EXT1_15") (pintype "passive"))
      (node (ref "Con1") (pin "16") (pinfunction "EXT2_16") (pintype "passive"))
      (node (ref "Con1") (pin "17") (pinfunction "EXT3_17") (pintype "passive"))
      (node (ref "Con1") (pin "20") (pinfunction "GND_20") (pintype "passive"))
      (node (ref "J1") (pin "1") (pintype "passive"))
      (node (ref "J2") (pin "1") (pintype "passive"))
      (node (ref "J3") (pin "2") (pinfunction "GND_2") (pintype "passive"))
      (node (ref "R10") (pin "1") (pintype "passive"))
      (node (ref "R11") (pin "1") (pintype "passive"))
      (node (ref "R20") (pin "1") (pinfunction "1_1") (pintype "passive"))
      (node (ref "R21") (pin "1") (pinfunction "1_1") (pintype "passive"))
      (node (ref "R22") (pin "1") (pinfunction "1_1") (pintype "passive"))
      (node (ref "R23") (pin "1") (pinfunction "1_1") (pintype "passive"))
      (node (ref "R4") (pin "1") (pintype "passive"))
      (node (ref "U1") (pin "2") (pinfunction "V-_2") (pintype "passive"))
      (node (ref "U10") (pin "1") (pinfunction "GND_1") (pintype "passive"))
      (node (ref "U11") (pin "20") (pinfunction "GND_20") (pintype "passive"))
      (node (ref "U2") (pin "2") (pinfunction "V-_2") (pintype "passive"))
      (node (ref "U3") (pin "2") (pinfunction "AGND2_2") (pintype "passive"))
      (node (ref "U3") (pin "42") (pinfunction "DGND_42") (pintype "passive"))
      (node (ref "U3") (pin "45") (pinfunction "AGND1_45") (pintype "passive"))
      (node (ref "U4") (pin "5") (pinfunction "V-_5") (pintype "passive"))
      (node (ref "U5") (pin "11") (pinfunction "GND_11") (pintype "power_in"))
      (node (ref "U5") (pin "12") (pinfunction "GND_12") (pintype "power_in"))
      (node (ref "U5") (pin "13") (pinfunction "GND_13") (pintype "power_in"))
      (node (ref "U6") (pin "22") (pinfunction "GND_22") (pintype "power_in"))
      (node (ref "U6") (pin "33") (pinfunction "GND_33") (pintype "power_in"))
      (node (ref "U6") (pin "44") (pinfunction "GND_44") (pintype "power_in"))
      (node (ref "U6") (pin "56") (pinfunction "GND_56") (pintype "power_in"))
      (node (ref "U6") (pin "6") (pinfunction "GND_6") (pintype "power_in"))
      (node (ref "U6") (pin "72") (pinfunction "GND_72") (pintype "power_in"))
      (node (ref "U6") (pin "79") (pinfunction "GND_79") (pintype "power_in"))
      (node (ref "U6") (pin "92") (pinfunction "GND_92") (pintype "power_in"))
      (node (ref "U7") (pin "1") (pinfunction "~{OE1}_1") (pintype "input"))
      (node (ref "U7") (pin "10") (pinfunction "GND_10") (pintype "power_in"))
      (node (ref "U7") (pin "19") (pinfunction "~{OE2}_19") (pintype "input"))
      (node (ref "U8") (pin "11") (pinfunction "GND_11") (pintype "power_in"))
      (node (ref "U8") (pin "12") (pinfunction "GND_12") (pintype "power_in"))
      (node (ref "U8") (pin "13") (pinfunction "GND_13") (pintype "power_in"))
      (node (ref "U9") (pin "1") (pinfunction "~{OE1}_1") (pintype "input"))
      (node (ref "U9") (pin "10") (pinfunction "GND_10") (pintype "power_in"))
      (node (ref "U9") (pin "19") (pinfunction "~{OE2}_19") (pintype "input"))
      (node (ref "U9") (pin "2") (pinfunction "A1_2") (pintype "input"))
      (node (ref "U9") (pin "9") (pinfunction "A8_9") (pintype "input"))
    )
    (net (code "111") (name "Net-(C14-Pad2)") (class "Default")
      (node (ref "C14") (pin "2") (pintype "power_in"))
      (node (ref "L1") (pin "2") (pinfunction "2_2") (pintype "passive"))
    )
    (net (code "112") (name "Net-(C17-Pad1)") (class "Default")
      (node (ref "C17") (pin "1") (pinfunction "1_1") (pintype "passive"))
      (node (ref "R13") (pin "2") (pintype "passive"))
    )
    (net (code "113") (name "Net-(C18-Pad2)") (class "Default")
      (node (ref "C18") (pin "2") (pinfunction "2_2") (pintype "passive"))
      (node (ref "R17") (pin "2") (pintype "passive"))
    )
    (net (code "114") (name "Net-(C19-Pad1)") (class "Default")
      (node (ref "C19") (pin "1") (pinfunction "1_1") (pintype "passive"))
      (node (ref "R14") (pin "2") (pintype "passive"))
    )
    (net (code "115") (name "Net-(C20-Pad2)") (class "Default")
      (node (ref "C20") (pin "2") (pintype "power_in"))
      (node (ref "R18") (pin "2") (pintype "passive"))
    )
    (net (code "116") (name "Net-(C21-Pad1)") (class "Default")
      (node (ref "C21") (pin "1") (pinfunction "1_1") (pintype "passive"))
      (node (ref "R15") (pin "2") (pintype "passive"))
    )
    (net (code "117") (name "Net-(C22-Pad2)") (class "Default")
      (node (ref "C22") (pin "2") (pinfunction "2_2") (pintype "passive"))
      (node (ref "R16") (pin "2") (pintype "passive"))
    )
    (net (code "118") (name "Net-(Con1-A8)") (class "Default")
      (node (ref "Con1") (pin "30") (pinfunction "A8_30") (pintype "passive"))
      (node (ref "U11") (pin "30") (pinfunction "A8_30") (pintype "passive"))
    )
    (net (code "119") (name "Net-(Con1-A9)") (class "Default")
      (node (ref "Con1") (pin "29") (pinfunction "A9_29") (pintype "passive"))
      (node (ref "U11") (pin "29") (pinfunction "A9_29") (pintype "passive"))
    )
    (net (code "120") (name "Net-(Con1-A10)") (class "Default")
      (node (ref "Con1") (pin "28") (pinfunction "A10_28") (pintype "passive"))
      (node (ref "U11") (pin "28") (pinfunction "A10_28") (pintype "passive"))
    )
    (net (code "121") (name "Net-(Con1-A11)") (class "Default")
      (node (ref "Con1") (pin "27") (pinfunction "A11_27") (pintype "passive"))
      (node (ref "U11") (pin "27") (pinfunction "A11_27") (pintype "passive"))
    )
    (net (code "122") (name "Net-(Con1-A12)") (class "Default")
      (node (ref "Con1") (pin "26") (pinfunction "A12_26") (pintype "passive"))
      (node (ref "U11") (pin "26") (pinfunction "A12_26") (pintype "passive"))
    )
    (net (code "123") (name "Net-(Con1-A13)") (class "Default")
      (node (ref "Con1") (pin "25") (pinfunction "A13_25") (pintype "passive"))
      (node (ref "U11") (pin "25") (pinfunction "A13_25") (pintype "passive"))
    )
    (net (code "124") (name "Net-(Con1-AD0)") (class "Default")
      (node (ref "Con1") (pin "38") (pinfunction "AD0_38") (pintype "passive"))
      (node (ref "U11") (pin "38") (pinfunction "AD0_38") (pintype "passive"))
    )
    (net (code "125") (name "Net-(Con1-AD1)") (class "Default")
      (node (ref "Con1") (pin "37") (pinfunction "AD1_37") (pintype "passive"))
      (node (ref "U11") (pin "37") (pinfunction "AD1_37") (pintype "passive"))
    )
    (net (code "126") (name "Net-(Con1-AD2)") (class "Default")
      (node (ref "Con1") (pin "36") (pinfunction "AD2_36") (pintype "passive"))
      (node (ref "U11") (pin "36") (pinfunction "AD2_36") (pintype "passive"))
    )
    (net (code "127") (name "Net-(Con1-AD3)") (class "Default")
      (node (ref "Con1") (pin "35") (pinfunction "AD3_35") (pintype "passive"))
      (node (ref "U11") (pin "35") (pinfunction "AD3_35") (pintype "passive"))
    )
    (net (code "128") (name "Net-(Con1-AD4)") (class "Default")
      (node (ref "Con1") (pin "34") (pinfunction "AD4_34") (pintype "passive"))
      (node (ref "U11") (pin "34") (pinfunction "AD4_34") (pintype "passive"))
    )
    (net (code "129") (name "Net-(Con1-AD5)") (class "Default")
      (node (ref "Con1") (pin "33") (pinfunction "AD5_33") (pintype "passive"))
      (node (ref "U11") (pin "33") (pinfunction "AD5_33") (pintype "passive"))
    )
    (net (code "130") (name "Net-(Con1-AD6)") (class "Default")
      (node (ref "Con1") (pin "32") (pinfunction "AD6_32") (pintype "passive"))
      (node (ref "U11") (pin "32") (pinfunction "AD6_32") (pintype "passive"))
    )
    (net (code "131") (name "Net-(Con1-AD7)") (class "Default")
      (node (ref "Con1") (pin "31") (pinfunction "AD7_31") (pintype "passive"))
      (node (ref "U11") (pin "31") (pinfunction "AD7_31") (pintype "passive"))
    )
    (net (code "132") (name "Net-(Con1-ALE)") (class "Default")
      (node (ref "Con1") (pin "39") (pinfunction "ALE_39") (pintype "passive"))
      (node (ref "U11") (pin "39") (pinfunction "ALE_39") (pintype "passive"))
    )
    (net (code "133") (name "Net-(Con1-CLK)") (class "Default")
      (node (ref "Con1") (pin "18") (pinfunction "CLK_18") (pintype "passive"))
      (node (ref "R5") (pin "1") (pintype "passive"))
    )
    (net (code "134") (name "Net-(Con1-{slash}R)") (class "Default")
      (node (ref "Con1") (pin "24") (pinfunction "/R_24") (pintype "passive"))
      (node (ref "U11") (pin "24") (pinfunction "/R_24") (pintype "passive"))
    )
    (net (code "135") (name "Net-(Con1-{slash}W)") (class "Default")
      (node (ref "Con1") (pin "23") (pinfunction "/W_23") (pintype "passive"))
      (node (ref "U11") (pin "23") (pinfunction "/W_23") (pintype "passive"))
    )
    (net (code "136") (name "Net-(R6-Pad2)") (class "Default")
      (node (ref "R6") (pin "2") (pintype "passive"))
      (node (ref "U4") (pin "6") (pintype "passive"))
    )
    (net (code "137") (name "Net-(R7-Pad2)") (class "Default")
      (node (ref "R7") (pin "2") (pintype "passive"))
      (node (ref "U4") (pin "7") (pintype "passive"))
    )
    (net (code "138") (name "Net-(U1-+)") (class "Default")
      (node (ref "R1") (pin "2") (pintype "passive"))
      (node (ref "U1") (pin "3") (pinfunction "+_3") (pintype "passive"))
    )
    (net (code "139") (name "Net-(U1--)") (class "Default")
      (node (ref "R2") (pin "2") (pintype "passive"))
      (node (ref "U1") (pin "1") (pintype "passive"))
      (node (ref "U1") (pin "4") (pinfunction "-_4") (pintype "passive"))
      (node (ref "U4") (pin "1") (pinfunction "+_1") (pintype "passive"))
      (node (ref "U4") (pin "3") (pinfunction "+_3") (pintype "passive"))
    )
    (net (code "140") (name "Net-(U2-+)") (class "Default")
      (node (ref "C3") (pin "2") (pintype "power_in"))
      (node (ref "R2") (pin "1") (pintype "passive"))
      (node (ref "U2") (pin "3") (pinfunction "+_3") (pintype "passive"))
    )
    (net (code "141") (name "Net-(U2--)") (class "Default")
      (node (ref "C4") (pin "2") (pintype "power_in"))
      (node (ref "R3") (pin "1") (pintype "passive"))
      (node (ref "R4") (pin "2") (pintype "passive"))
      (node (ref "U2") (pin "4") (pinfunction "-_4") (pintype "passive"))
    )
    (net (code "142") (name "Net-(U3-BCLAMP)") (class "Default")
      (node (ref "C13") (pin "1") (pintype "power_in"))
      (node (ref "U3") (pin "1") (pinfunction "BCLAMP_1") (pintype "passive"))
    )
    (net (code "143") (name "Net-(U3-BOUT)") (class "Default")
      (node (ref "R15") (pin "1") (pintype "passive"))
      (node (ref "U3") (pin "5") (pinfunction "BOUT_5") (pintype "passive"))
    )
    (net (code "144") (name "Net-(U3-COUT)") (class "Default")
      (node (ref "R18") (pin "1") (pintype "passive"))
      (node (ref "U3") (pin "7") (pinfunction "COUT_7") (pintype "passive"))
    )
    (net (code "145") (name "Net-(U3-GCLAMP)") (class "Default")
      (node (ref "C12") (pin "2") (pintype "power_in"))
      (node (ref "U3") (pin "48") (pinfunction "GCLAMP_48") (pintype "passive"))
    )
    (net (code "146") (name "Net-(U3-GOUT)") (class "Default")
      (node (ref "R14") (pin "1") (pintype "passive"))
      (node (ref "U3") (pin "4") (pinfunction "GOUT_4") (pintype "passive"))
    )
    (net (code "147") (name "Net-(U3-NT{slash}PAL)") (class "Default")
      (node (ref "R12") (pin "2") (pintype "passive"))
      (node (ref "U3") (pin "13") (pinfunction "NT/PAL_13") (pintype "power_in"))
    )
    (net (code "148") (name "Net-(U3-RCLAMP)") (class "Default")
      (node (ref "C9") (pin "2") (pintype "power_in"))
      (node (ref "U3") (pin "46") (pinfunction "RCLAMP_46") (pintype "passive"))
    )
    (net (code "149") (name "Net-(U3-ROUT)") (class "Default")
      (node (ref "R13") (pin "1") (pintype "passive"))
      (node (ref "U3") (pin "3") (pinfunction "ROUT_3") (pintype "passive"))
    )
    (net (code "150") (name "Net-(U3-VOUT)") (class "Default")
      (node (ref "R17") (pin "1") (pintype "passive"))
      (node (ref "U3") (pin "8") (pinfunction "VOUT_8") (pintype "passive"))
    )
    (net (code "151") (name "Net-(U3-VREFOUT)") (class "Default")
      (node (ref "C6") (pin "2") (pintype "power_in"))
      (node (ref "U3") (pin "43") (pinfunction "VREFOUT_43") (pintype "passive"))
    )
    (net (code "152") (name "Net-(U3-YOUT)") (class "Default")
      (node (ref "R16") (pin "1") (pintype "passive"))
      (node (ref "U3") (pin "6") (pinfunction "YOUT_6") (pintype "passive"))
    )
    (net (code "153") (name "Net-(U3-YTRAP)") (class "Default")
      (node (ref "L1") (pin "1") (pinfunction "1_1") (pintype "passive"))
      (node (ref "U3") (pin "10") (pinfunction "YTRAP_10") (pintype "passive"))
    )
    (net (code "154") (name "Net-(U4A--)") (class "Default")
      (node (ref "C8") (pin "2") (pintype "power_in"))
      (node (ref "R11") (pin "2") (pintype "passive"))
      (node (ref "R9") (pin "1") (pintype "passive"))
      (node (ref "U4") (pin "2") (pinfunction "-_2") (pintype "passive"))
    )
    (net (code "155") (name "Net-(U4B--)") (class "Default")
      (node (ref "C7") (pin "2") (pintype "power_in"))
      (node (ref "R10") (pin "2") (pintype "passive"))
      (node (ref "R8") (pin "1") (pintype "passive"))
      (node (ref "U4") (pin "4") (pinfunction "-_4") (pintype "passive"))
    )
    (net (code "156") (name "unconnected-(U3-NC-Pad11)") (class "Default")
      (node (ref "U3") (pin "11") (pinfunction "NC_11") (pintype "passive"))
    )
    (net (code "157") (name "unconnected-(U3-NC-Pad12)") (class "Default")
      (node (ref "U3") (pin "12") (pinfunction "NC_12") (pintype "passive"))
    )
    (net (code "158") (name "unconnected-(U3-NC-Pad44)") (class "Default")
      (node (ref "U3") (pin "44") (pinfunction "NC_44") (pintype "passive"))
    )
    (net (code "159") (name "unconnected-(U5-VCCB-Pad23)") (class "Default")
      (node (ref "U5") (pin "23") (pinfunction "VCCB_23") (pintype "power_in"))
    )
    (net (code "160") (name "unconnected-(U6-NC-Pad89)") (class "Default")
      (node (ref "U6") (pin "89") (pinfunction "NC_89") (pintype "passive"))
    )
    (net (code "161") (name "unconnected-(U6-PB6D{slash}SO{slash}SPISO-Pad32)") (class "Default")
      (node (ref "U6") (pin "32") (pinfunction "PB6D/SO/SPISO_32") (pintype "passive"))
    )
    (net (code "162") (name "unconnected-(U6-PL8A-Pad16)") (class "Default")
      (node (ref "U6") (pin "16") (pinfunction "PL8A_16") (pintype "passive"))
    )
    (net (code "163") (name "unconnected-(U6-PL8B-Pad17)") (class "Default")
      (node (ref "U6") (pin "17") (pinfunction "PL8B_17") (pintype "passive"))
    )
    (net (code "164") (name "unconnected-(U6-PL8C-Pad18)") (class "Default")
      (node (ref "U6") (pin "18") (pinfunction "PL8C_18") (pintype "passive"))
    )
    (net (code "165") (name "unconnected-(U6-PL8D-Pad19)") (class "Default")
      (node (ref "U6") (pin "19") (pinfunction "PL8D_19") (pintype "passive"))
    )
    (net (code "166") (name "unconnected-(U6-PL9A{slash}PCLKT3_0-Pad20)") (class "Default")
      (node (ref "U6") (pin "20") (pinfunction "PL9A/PCLKT3_0_20") (pintype "passive"))
    )
    (net (code "167") (name "unconnected-(U6-PL9B{slash}PCLKC3_0-Pad21)") (class "Default")
      (node (ref "U6") (pin "21") (pinfunction "PL9B/PCLKC3_0_21") (pintype "passive"))
    )
    (net (code "168") (name "unconnected-(U6-PL10C-Pad24)") (class "Default")
      (node (ref "U6") (pin "24") (pinfunction "PL10C_24") (pintype "passive"))
    )
    (net (code "169") (name "unconnected-(U6-PL10D-Pad25)") (class "Default")
      (node (ref "U6") (pin "25") (pinfunction "PL10D_25") (pintype "passive"))
    )
    (net (code "170") (name "unconnected-(U6-PR10C_DQ1-Pad52)") (class "Default")
      (node (ref "U6") (pin "52") (pinfunction "PR10C_DQ1_52") (pintype "passive"))
    )
    (net (code "171") (name "unconnected-(U8-VCCB-Pad23)") (class "Default")
      (node (ref "U8") (pin "23") (pinfunction "VCCB_23") (pintype "power_in"))
    )
    (net (code "172") (name "unconnected-(U9-Y1-Pad18)") (class "Default")
      (node (ref "U9") (pin "18") (pinfunction "Y1_18") (pintype "output"))
    )
    (net (code "173") (name "unconnected-(U9-Y8-Pad11)") (class "Default")
      (node (ref "U9") (pin "11") (pinfunction "Y8_11") (pintype "output"))
    )
  )
)
